# mavroOBD.net
KiCad netlist of a schematic drawn in EAGLE
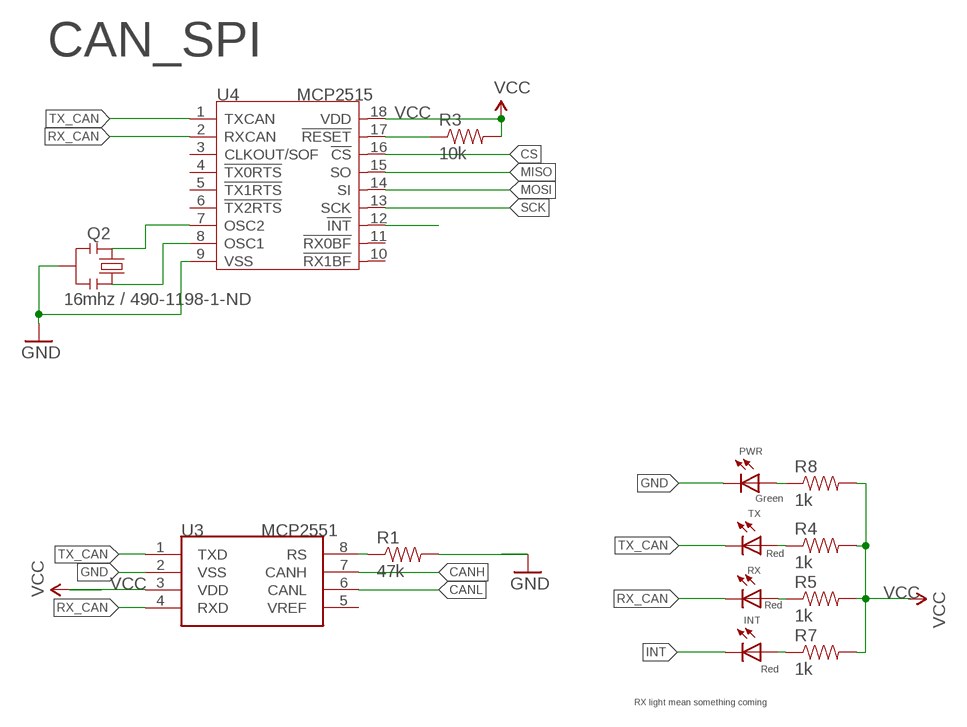
[diagram p0: schematic, sheet 1]

(export (version "E")
  (design (tool "Eeschema 10.0.6"))
  (components
    (comp (ref "INT")
      (value "Red")
      (footprint "eagle-import:0603-LED-ALT1")
      (libsource (lib "eagle-import") (part "LED"))
    )
    (comp (ref "PWR")
      (value "Green")
      (footprint "eagle-import:0603-LED-ALT1")
      (libsource (lib "eagle-import") (part "LED"))
    )
    (comp (ref "Q2")
      (value "16mhz / 490-1198-1-ND")
      (footprint "eagle-import:RESONATOR-SMD-1_1")
      (libsource (lib "eagle-import") (part "RESONATOR1{colon}1"))
    )
    (comp (ref "R1")
      (value "47k")
      (footprint "eagle-import:0603-RES")
      (libsource (lib "eagle-import") (part "RESISTOR0603-RES"))
    )
    (comp (ref "R3")
      (value "10k")
      (footprint "eagle-import:0603-RES")
      (libsource (lib "eagle-import") (part "RESISTOR0603-RES"))
    )
    (comp (ref "R4")
      (value "1k")
      (footprint "eagle-import:0603-RES")
      (libsource (lib "eagle-import") (part "RESISTOR0603-RES"))
    )
    (comp (ref "R5")
      (value "1k")
      (footprint "eagle-import:0603-RES")
      (libsource (lib "eagle-import") (part "RESISTOR0603-RES"))
    )
    (comp (ref "R7")
      (value "1k")
      (footprint "eagle-import:0603-RES")
      (libsource (lib "eagle-import") (part "RESISTOR0603-RES"))
    )
    (comp (ref "R8")
      (value "1k")
      (footprint "eagle-import:0603-RES")
      (libsource (lib "eagle-import") (part "RESISTOR0603-RES"))
    )
    (comp (ref "RX")
      (value "Red")
      (footprint "eagle-import:0603-LED-ALT1")
      (libsource (lib "eagle-import") (part "LED"))
    )
    (comp (ref "TX")
      (value "Red")
      (footprint "eagle-import:0603-LED-ALT1")
      (libsource (lib "eagle-import") (part "LED"))
    )
    (comp (ref "U3")
      (value "MCP2551")
      (footprint "eagle-import:SOIC8-6.0")
      (libsource (lib "eagle-import") (part "MCP2551-SOIC8"))
    )
    (comp (ref "U4")
      (value "MCP2515")
      (footprint "eagle-import:SOIC18")
      (libsource (lib "eagle-import") (part "MCP2515-SOIC18"))
    )
  )
  (nets
    (net (code "1") (name "CANH") (class "Default")
      (node (ref "U3") (pin "7") (pinfunction "CANH_7") (pintype "bidirectional"))
    )
    (net (code "2") (name "CANL") (class "Default")
      (node (ref "U3") (pin "6") (pinfunction "CANL_6") (pintype "bidirectional"))
    )
    (net (code "3") (name "CS") (class "Default")
      (node (ref "U4") (pin "16") (pinfunction "~{CS}_16") (pintype "input"))
    )
    (net (code "4") (name "GND") (class "Default")
      (node (ref "PWR") (pin "C") (pinfunction "C_C") (pintype "passive"))
      (node (ref "Q2") (pin "2") (pinfunction "2_2") (pintype "passive"))
      (node (ref "R1") (pin "2") (pinfunction "2_2") (pintype "passive"))
      (node (ref "U3") (pin "2") (pinfunction "VSS_2") (pintype "bidirectional"))
      (node (ref "U4") (pin "9") (pinfunction "VSS_9") (pintype "power_in"))
    )
    (net (code "5") (name "INT") (class "Default")
      (node (ref "INT") (pin "C") (pinfunction "C_C") (pintype "passive"))
      (node (ref "U4") (pin "12") (pinfunction "~{INT}_12") (pintype "output"))
    )
    (net (code "6") (name "MISO") (class "Default")
      (node (ref "U4") (pin "15") (pinfunction "SO_15") (pintype "output"))
    )
    (net (code "7") (name "MOSI") (class "Default")
      (node (ref "U4") (pin "14") (pinfunction "SI_14") (pintype "input"))
    )
    (net (code "8") (name "Net-(INT-PadA)") (class "Default")
      (node (ref "INT") (pin "A") (pinfunction "A_A") (pintype "passive"))
      (node (ref "R7") (pin "1") (pinfunction "1_1") (pintype "passive"))
    )
    (net (code "9") (name "Net-(PWR-PadA)") (class "Default")
      (node (ref "PWR") (pin "A") (pinfunction "A_A") (pintype "passive"))
      (node (ref "R8") (pin "1") (pinfunction "1_1") (pintype "passive"))
    )
    (net (code "10") (name "Net-(R4-Pad1)") (class "Default")
      (node (ref "R4") (pin "1") (pinfunction "1_1") (pintype "passive"))
      (node (ref "TX") (pin "A") (pinfunction "A_A") (pintype "passive"))
    )
    (net (code "11") (name "Net-(R5-Pad1)") (class "Default")
      (node (ref "R5") (pin "1") (pinfunction "1_1") (pintype "passive"))
      (node (ref "RX") (pin "A") (pinfunction "A_A") (pintype "passive"))
    )
    (net (code "12") (name "Net-(U3-RS)") (class "Default")
      (node (ref "R1") (pin "1") (pinfunction "1_1") (pintype "passive"))
      (node (ref "U3") (pin "8") (pinfunction "RS_8") (pintype "bidirectional"))
    )
    (net (code "13") (name "Net-(U4-OSC1)") (class "Default")
      (node (ref "Q2") (pin "3") (pinfunction "3_3") (pintype "passive"))
      (node (ref "U4") (pin "8") (pinfunction "OSC1_8") (pintype "input"))
    )
    (net (code "14") (name "Net-(U4-OSC2)") (class "Default")
      (node (ref "Q2") (pin "1") (pinfunction "1_1") (pintype "passive"))
      (node (ref "U4") (pin "7") (pinfunction "OSC2_7") (pintype "output"))
    )
    (net (code "15") (name "Net-(U4-~{RESET})") (class "Default")
      (node (ref "R3") (pin "1") (pinfunction "1_1") (pintype "passive"))
      (node (ref "U4") (pin "17") (pinfunction "~{RESET}_17") (pintype "input"))
    )
    (net (code "16") (name "RX_CAN") (class "Default")
      (node (ref "RX") (pin "C") (pinfunction "C_C") (pintype "passive"))
      (node (ref "U3") (pin "4") (pinfunction "RXD_4") (pintype "bidirectional"))
      (node (ref "U4") (pin "2") (pinfunction "RXCAN_2") (pintype "input"))
    )
    (net (code "17") (name "SCK") (class "Default")
      (node (ref "U4") (pin "13") (pinfunction "SCK_13") (pintype "input"))
    )
    (net (code "18") (name "TX_CAN") (class "Default")
      (node (ref "TX") (pin "C") (pinfunction "C_C") (pintype "passive"))
      (node (ref "U3") (pin "1") (pinfunction "TXD_1") (pintype "bidirectional"))
      (node (ref "U4") (pin "1") (pinfunction "TXCAN_1") (pintype "output"))
    )
    (net (code "19") (name "VCC") (class "Default")
      (node (ref "R3") (pin "2") (pinfunction "2_2") (pintype "passive"))
      (node (ref "R4") (pin "2") (pinfunction "2_2") (pintype "passive"))
      (node (ref "R5") (pin "2") (pinfunction "2_2") (pintype "passive"))
      (node (ref "R7") (pin "2") (pinfunction "2_2") (pintype "passive"))
      (node (ref "R8") (pin "2") (pinfunction "2_2") (pintype "passive"))
      (node (ref "U3") (pin "3") (pinfunction "VDD_3") (pintype "bidirectional"))
      (node (ref "U4") (pin "18") (pinfunction "VDD_18") (pintype "power_in"))
    )
    (net (code "20") (name "unconnected-(U3-VREF-Pad5)") (class "Default")
      (node (ref "U3") (pin "5") (pinfunction "VREF_5") (pintype "bidirectional"))
    )
    (net (code "21") (name "unconnected-(U4-CLKOUT{slash}SOF-Pad3)") (class "Default")
      (node (ref "U4") (pin "3") (pinfunction "CLKOUT/SOF_3") (pintype "output"))
    )
    (net (code "22") (name "unconnected-(U4-~{RX0BF}-Pad11)") (class "Default")
      (node (ref "U4") (pin "11") (pinfunction "~{RX0BF}_11") (pintype "output"))
    )
    (net (code "23") (name "unconnected-(U4-~{RX1BF}-Pad10)") (class "Default")
      (node (ref "U4") (pin "10") (pinfunction "~{RX1BF}_10") (pintype "output"))
    )
    (net (code "24") (name "unconnected-(U4-~{TX0RTS}-Pad4)") (class "Default")
      (node (ref "U4") (pin "4") (pinfunction "~{TX0RTS}_4") (pintype "input"))
    )
    (net (code "25") (name "unconnected-(U4-~{TX1RTS}-Pad5)") (class "Default")
      (node (ref "U4") (pin "5") (pinfunction "~{TX1RTS}_5") (pintype "input"))
    )
    (net (code "26") (name "unconnected-(U4-~{TX2RTS}-Pad6)") (class "Default")
      (node (ref "U4") (pin "6") (pinfunction "~{TX2RTS}_6") (pintype "input"))
    )
  )
)
